# mcu.net
KiCad netlist of a schematic drawn in Altium Designer
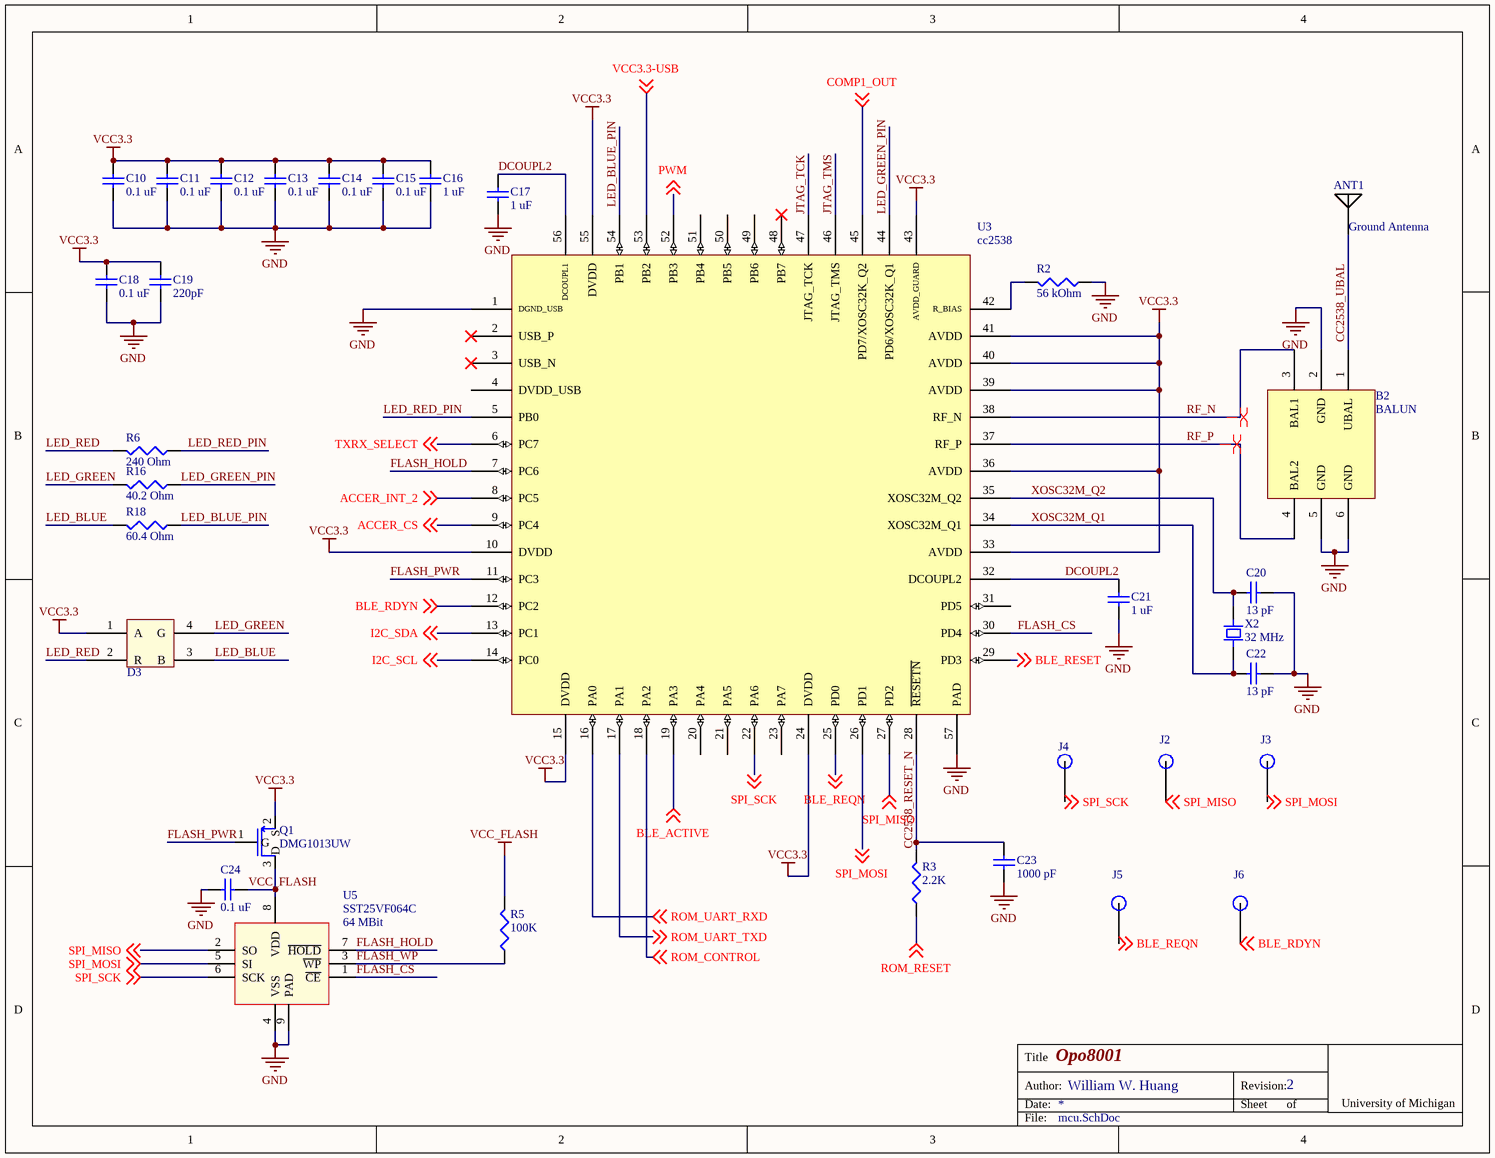
[diagram p0: mcu.SchDoc]

(export (version "E")
  (design (tool "Eeschema 10.0.6"))
  (components
    (comp (ref "ANT1")
      (value "Ground Antenna")
      (footprint "SMD Ground Antenna")
      (description "Molex 2.4 GHz SMD On-Ground Antenna")
      (libsource (lib "opo_general") (part "Molex Antenna"))
    )
    (comp (ref "B2")
      (value "BALUN")
      (footprint "2450BM15A0002")
      (description "Johanson CC253X Balun")
      (fields (field (name "MFR") "Johanson Technology") (field (name "MFR PART NUMBER") "2450BM15A0002"))
      (libsource (lib "opo_general") (part "cc2538_Balun"))
    )
    (comp (ref "C10")
      (value "0.1 uF")
      (footprint "0402")
      (description "Ceramic capacitor, 0.1u, 0402 package")
      (fields (field (name "TOLERANCE") "10%") (field (name "Comment") "Ceramic capacitor"))
      (libsource (lib "rlc") (part "C_0.1u_0402_ceramic"))
    )
    (comp (ref "C11")
      (value "0.1 uF")
      (footprint "0402")
      (description "Ceramic capacitor, 0.1u, 0402 package")
      (fields (field (name "TOLERANCE") "10%") (field (name "Comment") "Ceramic capacitor"))
      (libsource (lib "rlc") (part "C_0.1u_0402_ceramic"))
    )
    (comp (ref "C12")
      (value "0.1 uF")
      (footprint "0402")
      (description "Ceramic capacitor, 0.1u, 0402 package")
      (fields (field (name "TOLERANCE") "10%") (field (name "Comment") "Ceramic capacitor"))
      (libsource (lib "rlc") (part "C_0.1u_0402_ceramic"))
    )
    (comp (ref "C13")
      (value "0.1 uF")
      (footprint "0402")
      (description "Ceramic capacitor, 0.1u, 0402 package")
      (fields (field (name "TOLERANCE") "10%") (field (name "Comment") "Ceramic capacitor"))
      (libsource (lib "rlc") (part "C_0.1u_0402_ceramic"))
    )
    (comp (ref "C14")
      (value "0.1 uF")
      (footprint "0402")
      (description "Ceramic capacitor, 0.1u, 0402 package")
      (fields (field (name "TOLERANCE") "10%") (field (name "Comment") "Ceramic capacitor"))
      (libsource (lib "rlc") (part "C_0.1u_0402_ceramic"))
    )
    (comp (ref "C15")
      (value "0.1 uF")
      (footprint "0402")
      (description "Ceramic capacitor, 0.1u, 0402 package")
      (fields (field (name "TOLERANCE") "10%") (field (name "Comment") "Ceramic capacitor"))
      (libsource (lib "rlc") (part "C_0.1u_0402_ceramic"))
    )
    (comp (ref "C16")
      (value "1 uF")
      (footprint "0402")
      (description "Ceramic capacitor, 1 uF, 0402 package")
      (fields (field (name "TOLERANCE") "10%") (field (name "Comment") "Ceramic capacitor"))
      (libsource (lib "rlc") (part "C_1u_0402_ceramic"))
    )
    (comp (ref "C17")
      (value "1 uF")
      (footprint "0402")
      (description "Ceramic capacitor, 1 uF, 0402 package")
      (fields (field (name "TOLERANCE") "10%") (field (name "Comment") "Ceramic capacitor"))
      (libsource (lib "rlc") (part "C_1u_0402_ceramic"))
    )
    (comp (ref "C18")
      (value "0.1 uF")
      (footprint "0402")
      (description "Ceramic capacitor, 0.1u, 0402 package")
      (fields (field (name "TOLERANCE") "10%") (field (name "Comment") "Ceramic capacitor"))
      (libsource (lib "rlc") (part "C_0.1u_0402_ceramic"))
    )
    (comp (ref "C19")
      (value "220pF")
      (footprint "0402")
      (description "220pF 5% 50 V C0G NP0 0402 ceramic cap")
      (fields (field (name "MFR") "Murata") (field (name "MFR PART NUMBER") "GRM1555C1H221JA01D"))
      (libsource (lib "rlc") (part "C_220pf_0402_ceramic"))
    )
    (comp (ref "C20")
      (value "13 pF")
      (footprint "0402")
      (description "13pf, 50V, 2%, c0G, NP0, 0402, ceramic")
      (fields (field (name "MFR") "Murata") (field (name "MFR PART NUMBER") "GRM1555C1H130GA01D"))
      (libsource (lib "rlc") (part "C_13p_0402"))
    )
    (comp (ref "C21")
      (value "1 uF")
      (footprint "0402")
      (description "Ceramic capacitor, 1 uF, 0402 package")
      (fields (field (name "TOLERANCE") "10%") (field (name "Comment") "Ceramic capacitor"))
      (libsource (lib "rlc") (part "C_1u_0402_ceramic"))
    )
    (comp (ref "C22")
      (value "13 pF")
      (footprint "0402")
      (description "13pf, 50V, 2%, c0G, NP0, 0402, ceramic")
      (fields (field (name "MFR") "Murata") (field (name "MFR PART NUMBER") "GRM1555C1H130GA01D"))
      (libsource (lib "rlc") (part "C_13p_0402"))
    )
    (comp (ref "C23")
      (value "1000 pF")
      (footprint "0402")
      (description "Ceramic capacitor, 1000 pF, 0402 package")
      (fields (field (name "TOLERANCE") "10%") (field (name "Comment") "Ceramic capacitor"))
      (libsource (lib "rlc") (part "C_1000p_0402_ceramic"))
    )
    (comp (ref "C24")
      (value "0.1 uF")
      (footprint "0402")
      (description "Ceramic capacitor, 0.1u, 0402 package")
      (fields (field (name "TOLERANCE") "10%") (field (name "Comment") "Ceramic capacitor"))
      (libsource (lib "rlc") (part "C_0.1u_0402_ceramic"))
    )
    (comp (ref "D3")
      (value "Tri Color LED")
      (footprint "0404")
      (description "LED, RGB, 0404")
      (libsource (lib "rlc") (part "D_LED_RGB_0404"))
    )
    (comp (ref "J2")
      (value "RCU 0603 SMD Testpoint")
      (footprint "RCU_0603")
      (description "0603 SMD Testpoint")
      (libsource (lib "connectors") (part "Testpoint-0603"))
    )
    (comp (ref "J3")
      (value "RCU 0603 SMD Testpoint")
      (footprint "RCU_0603")
      (description "0603 SMD Testpoint")
      (libsource (lib "connectors") (part "Testpoint-0603"))
    )
    (comp (ref "J4")
      (value "RCU 0603 SMD Testpoint")
      (footprint "RCU_0603")
      (description "0603 SMD Testpoint")
      (libsource (lib "connectors") (part "Testpoint-0603"))
    )
    (comp (ref "J5")
      (value "RCU 0603 SMD Testpoint")
      (footprint "RCU_0603")
      (description "0603 SMD Testpoint")
      (libsource (lib "connectors") (part "Testpoint-0603"))
    )
    (comp (ref "J6")
      (value "RCU 0603 SMD Testpoint")
      (footprint "RCU_0603")
      (description "0603 SMD Testpoint")
      (libsource (lib "connectors") (part "Testpoint-0603"))
    )
    (comp (ref "Q1")
      (value "DMG1013UW")
      (footprint "SC70-3")
      (description "P-CHANNEL ENHANCEMENT MODE MOSFET")
      (libsource (lib "opo_general") (part "DMG1013UW"))
    )
    (comp (ref "R2")
      (value "56 kOhm")
      (footprint "0402")
      (description "56 kOhm, 1%, .0603 W, 0402")
      (fields (field (name "MFR") "Rohm") (field (name "MFR PART NUMBER") "MCR01MRTF5602"))
      (libsource (lib "rlc") (part "R_56K_0402"))
    )
    (comp (ref "R3")
      (value "2.2K")
      (footprint "0402")
      (description "Chip resistor, 2.2K, 0402 package")
      (fields (field (name "TOLERANCE") "1%") (field (name "POWER") "1/16 W"))
      (libsource (lib "rlc") (part "R_2.2K_0402"))
    )
    (comp (ref "R5")
      (value "100K")
      (footprint "0402")
      (description "Chip resistor, 100K, 0402 package")
      (fields (field (name "TOLERANCE") "1%") (field (name "POWER") "1/16 W"))
      (libsource (lib "rlc") (part "R_100K_0402"))
    )
    (comp (ref "R6")
      (value "240 Ohm")
      (footprint "0402")
      (description "240 Ohm, 1%, .05W, 0402 Chip Resistor")
      (fields (field (name "Comment") "Chip resistor"))
      (libsource (lib "rlc") (part "R_240_0402"))
    )
    (comp (ref "R16")
      (value "40.2 Ohm")
      (footprint "0402")
      (description "40.2 Ohm 0402 1% Chip Resistor")
      (fields (field (name "Comment") "Chip Resistor"))
      (libsource (lib "rlc") (part "R_40.2_0402"))
    )
    (comp (ref "R18")
      (value "60.4 Ohm")
      (footprint "0402")
      (description "60.4 Ohm, .05W, 1% 0402 Chip Resistor")
      (fields (field (name "Comment") "Chip resistor"))
      (libsource (lib "rlc") (part "R_60.4_0402"))
    )
    (comp (ref "U3")
      (value "cc2538")
      (footprint "QFN50P800X800X100_HS-57N")
      (description "cc2538 MCU/802.15.4 radio")
      (libsource (lib "opo_general") (part "cc2538"))
    )
    (comp (ref "U5")
      (value "SST25VF064C")
      (footprint "WSON")
      (description "64 Mbit SPI Serial Dual I/O Flash")
      (fields (field (name "CAPACITY") "64 MBit"))
      (libsource (lib "opo_general") (part "SST25VF064C"))
    )
    (comp (ref "X2")
      (value "32 MHz")
      (footprint "FA-128")
      (description "32MHz, 10ppm, 10pF, 60 Ohm")
      (fields (field (name "MFR") "Epson") (field (name "MFR PART NUMBER") "FA-128 32.0000MF20X-K3"))
      (libsource (lib "opo_general") (part "X_32M_FA-128"))
    )
  )
  (nets
    (net (code "1") (name "/CC2538_RESET_N") (class "Default")
      (node (ref "C23") (pin "1") (pintype "passive"))
      (node (ref "R3") (pin "1") (pintype "passive"))
      (node (ref "U3") (pin "28") (pinfunction "~{RESETN}_28") (pintype "passive"))
    )
    (net (code "2") (name "/CC2538_UBAL") (class "Default")
      (node (ref "ANT1") (pin "1") (pintype "passive"))
      (node (ref "B2") (pin "1") (pinfunction "UBAL_1") (pintype "passive"))
    )
    (net (code "3") (name "/DCOUPL2") (class "Default")
      (node (ref "C17") (pin "1") (pintype "passive"))
      (node (ref "C21") (pin "1") (pintype "passive"))
      (node (ref "U3") (pin "32") (pinfunction "DCOUPL2_32") (pintype "power_in"))
      (node (ref "U3") (pin "56") (pinfunction "DCOUPL1_56") (pintype "power_in"))
    )
    (net (code "4") (name "/FLASH_CS") (class "Default")
      (node (ref "U3") (pin "30") (pinfunction "PD4_30") (pintype "bidirectional"))
      (node (ref "U5") (pin "1") (pinfunction "~{CE}_1") (pintype "passive"))
    )
    (net (code "5") (name "/FLASH_HOLD") (class "Default")
      (node (ref "U3") (pin "7") (pinfunction "PC6_7") (pintype "bidirectional"))
      (node (ref "U5") (pin "7") (pinfunction "~{HOLD}_7") (pintype "passive"))
    )
    (net (code "6") (name "/FLASH_PWR") (class "Default")
      (node (ref "Q1") (pin "1") (pinfunction "G_1") (pintype "passive"))
      (node (ref "U3") (pin "11") (pinfunction "PC3_11") (pintype "bidirectional"))
    )
    (net (code "7") (name "/FLASH_WP") (class "Default")
      (node (ref "R5") (pin "2") (pintype "passive"))
      (node (ref "U5") (pin "3") (pinfunction "~{WP}_3") (pintype "passive"))
    )
    (net (code "8") (name "/JTAG_TCK") (class "Default")
      (node (ref "U3") (pin "47") (pinfunction "JTAG_TCK_47") (pintype "passive"))
    )
    (net (code "9") (name "/JTAG_TMS") (class "Default")
      (node (ref "U3") (pin "46") (pinfunction "JTAG_TMS_46") (pintype "passive"))
    )
    (net (code "10") (name "/LED_BLUE") (class "Default")
      (node (ref "D3") (pin "3") (pinfunction "B_3") (pintype "passive"))
      (node (ref "R18") (pin "1") (pintype "passive"))
    )
    (net (code "11") (name "/LED_BLUE_PIN") (class "Default")
      (node (ref "R18") (pin "2") (pintype "passive"))
      (node (ref "U3") (pin "54") (pinfunction "PB1_54") (pintype "bidirectional"))
    )
    (net (code "12") (name "/LED_GREEN") (class "Default")
      (node (ref "D3") (pin "4") (pinfunction "G_4") (pintype "passive"))
      (node (ref "R16") (pin "1") (pintype "passive"))
    )
    (net (code "13") (name "/LED_GREEN_PIN") (class "Default")
      (node (ref "R16") (pin "2") (pintype "passive"))
      (node (ref "U3") (pin "44") (pinfunction "PD6/XOSC32K_Q1_44") (pintype "passive"))
    )
    (net (code "14") (name "/LED_RED") (class "Default")
      (node (ref "D3") (pin "2") (pinfunction "R_2") (pintype "passive"))
      (node (ref "R6") (pin "1") (pintype "passive"))
    )
    (net (code "15") (name "/LED_RED_PIN") (class "Default")
      (node (ref "R6") (pin "2") (pintype "passive"))
      (node (ref "U3") (pin "5") (pinfunction "PB0_5") (pintype "passive"))
    )
    (net (code "16") (name "/RF_N") (class "Default")
      (node (ref "B2") (pin "3") (pinfunction "BAL1_3") (pintype "passive"))
      (node (ref "U3") (pin "38") (pinfunction "RF_N_38") (pintype "passive"))
    )
    (net (code "17") (name "/RF_P") (class "Default")
      (node (ref "B2") (pin "4") (pinfunction "BAL2_4") (pintype "passive"))
      (node (ref "U3") (pin "37") (pinfunction "RF_P_37") (pintype "passive"))
    )
    (net (code "18") (name "/XOSC32M_Q1") (class "Default")
      (node (ref "C22") (pin "2") (pintype "passive"))
      (node (ref "U3") (pin "34") (pinfunction "XOSC32M_Q1_34") (pintype "passive"))
      (node (ref "X2") (pin "3") (pintype "passive"))
    )
    (net (code "19") (name "/XOSC32M_Q2") (class "Default")
      (node (ref "C20") (pin "1") (pintype "passive"))
      (node (ref "U3") (pin "35") (pinfunction "XOSC32M_Q2_35") (pintype "passive"))
      (node (ref "X2") (pin "1") (pintype "passive"))
    )
    (net (code "20") (name "ACCER_CS") (class "Default")
      (node (ref "U3") (pin "9") (pinfunction "PC4_9") (pintype "bidirectional"))
    )
    (net (code "21") (name "ACCER_INT_2") (class "Default")
      (node (ref "U3") (pin "8") (pinfunction "PC5_8") (pintype "bidirectional"))
    )
    (net (code "22") (name "BLE_ACTIVE") (class "Default")
      (node (ref "U3") (pin "19") (pinfunction "PA3_19") (pintype "bidirectional"))
    )
    (net (code "23") (name "BLE_RDYN") (class "Default")
      (node (ref "J6") (pin "1") (pinfunction "J_1") (pintype "passive"))
      (node (ref "U3") (pin "12") (pinfunction "PC2_12") (pintype "bidirectional"))
    )
    (net (code "24") (name "BLE_REQN") (class "Default")
      (node (ref "J5") (pin "1") (pinfunction "J_1") (pintype "passive"))
      (node (ref "U3") (pin "25") (pinfunction "PD0_25") (pintype "bidirectional"))
    )
    (net (code "25") (name "BLE_RESET") (class "Default")
      (node (ref "U3") (pin "29") (pinfunction "PD3_29") (pintype "bidirectional"))
    )
    (net (code "26") (name "COMP1_OUT") (class "Default")
      (node (ref "U3") (pin "45") (pinfunction "PD7/XOSC32K_Q2_45") (pintype "passive"))
    )
    (net (code "27") (name "GND") (class "Default")
      (node (ref "B2") (pin "2") (pinfunction "GND_2") (pintype "passive"))
      (node (ref "B2") (pin "5") (pinfunction "GND_5") (pintype "passive"))
      (node (ref "B2") (pin "6") (pinfunction "GND_6") (pintype "passive"))
      (node (ref "C10") (pin "2") (pintype "passive"))
      (node (ref "C11") (pin "2") (pintype "passive"))
      (node (ref "C12") (pin "2") (pintype "passive"))
      (node (ref "C13") (pin "2") (pintype "passive"))
      (node (ref "C14") (pin "2") (pintype "passive"))
      (node (ref "C15") (pin "2") (pintype "passive"))
      (node (ref "C16") (pin "2") (pintype "passive"))
      (node (ref "C17") (pin "2") (pintype "passive"))
      (node (ref "C18") (pin "2") (pintype "passive"))
      (node (ref "C19") (pin "2") (pintype "passive"))
      (node (ref "C20") (pin "2") (pintype "passive"))
      (node (ref "C21") (pin "2") (pintype "passive"))
      (node (ref "C22") (pin "1") (pintype "passive"))
      (node (ref "C23") (pin "2") (pintype "passive"))
      (node (ref "C24") (pin "1") (pintype "passive"))
      (node (ref "R2") (pin "2") (pintype "passive"))
      (node (ref "U3") (pin "1") (pinfunction "DGND_USB_1") (pintype "passive"))
      (node (ref "U3") (pin "57") (pinfunction "PAD_57") (pintype "passive"))
      (node (ref "U5") (pin "4") (pinfunction "VSS_4") (pintype "passive"))
      (node (ref "U5") (pin "9") (pinfunction "PAD_9") (pintype "passive"))
    )
    (net (code "28") (name "I2C_SCL") (class "Default")
      (node (ref "U3") (pin "14") (pinfunction "PC0_14") (pintype "bidirectional"))
    )
    (net (code "29") (name "I2C_SDA") (class "Default")
      (node (ref "U3") (pin "13") (pinfunction "PC1_13") (pintype "bidirectional"))
    )
    (net (code "30") (name "Net-(U3-R_BIAS)") (class "Default")
      (node (ref "R2") (pin "1") (pintype "passive"))
      (node (ref "U3") (pin "42") (pinfunction "R_BIAS_42") (pintype "passive"))
    )
    (net (code "31") (name "PWM") (class "Default")
      (node (ref "U3") (pin "52") (pinfunction "PB3_52") (pintype "bidirectional"))
    )
    (net (code "32") (name "ROM_CONTROL") (class "Default")
      (node (ref "U3") (pin "18") (pinfunction "PA2_18") (pintype "bidirectional"))
    )
    (net (code "33") (name "ROM_RESET") (class "Default") (node (ref "R3") (pin "2") (pintype "passive")))
    (net (code "34") (name "ROM_UART_RXD") (class "Default")
      (node (ref "U3") (pin "16") (pinfunction "PA0_16") (pintype "bidirectional"))
    )
    (net (code "35") (name "ROM_UART_TXD") (class "Default")
      (node (ref "U3") (pin "17") (pinfunction "PA1_17") (pintype "bidirectional"))
    )
    (net (code "36") (name "SPI_MISO") (class "Default")
      (node (ref "J2") (pin "1") (pinfunction "J_1") (pintype "passive"))
      (node (ref "U3") (pin "27") (pinfunction "PD2_27") (pintype "bidirectional"))
      (node (ref "U5") (pin "2") (pinfunction "SO_2") (pintype "passive"))
    )
    (net (code "37") (name "SPI_MOSI") (class "Default")
      (node (ref "J3") (pin "1") (pinfunction "J_1") (pintype "passive"))
      (node (ref "U3") (pin "26") (pinfunction "PD1_26") (pintype "bidirectional"))
      (node (ref "U5") (pin "5") (pinfunction "SI_5") (pintype "passive"))
    )
    (net (code "38") (name "SPI_SCK") (class "Default")
      (node (ref "J4") (pin "1") (pinfunction "J_1") (pintype "passive"))
      (node (ref "U3") (pin "22") (pinfunction "PA6_22") (pintype "bidirectional"))
      (node (ref "U5") (pin "6") (pinfunction "SCK_6") (pintype "passive"))
    )
    (net (code "39") (name "TXRX_SELECT") (class "Default")
      (node (ref "U3") (pin "6") (pinfunction "PC7_6") (pintype "bidirectional"))
    )
    (net (code "40") (name "VCC3.3") (class "Default")
      (node (ref "C10") (pin "1") (pintype "passive"))
      (node (ref "C11") (pin "1") (pintype "passive"))
      (node (ref "C12") (pin "1") (pintype "passive"))
      (node (ref "C13") (pin "1") (pintype "passive"))
      (node (ref "C14") (pin "1") (pintype "passive"))
      (node (ref "C15") (pin "1") (pintype "passive"))
      (node (ref "C16") (pin "1") (pintype "passive"))
      (node (ref "C18") (pin "1") (pintype "passive"))
      (node (ref "C19") (pin "1") (pintype "passive"))
      (node (ref "D3") (pin "1") (pinfunction "A_1") (pintype "passive"))
      (node (ref "Q1") (pin "2") (pinfunction "S_2") (pintype "passive"))
      (node (ref "U3") (pin "10") (pinfunction "DVDD_10") (pintype "power_in"))
      (node (ref "U3") (pin "15") (pinfunction "DVDD_15") (pintype "power_in"))
      (node (ref "U3") (pin "24") (pinfunction "DVDD_24") (pintype "power_in"))
      (node (ref "U3") (pin "33") (pinfunction "AVDD_33") (pintype "power_in"))
      (node (ref "U3") (pin "36") (pinfunction "AVDD_36") (pintype "power_in"))
      (node (ref "U3") (pin "39") (pinfunction "AVDD_39") (pintype "power_in"))
      (node (ref "U3") (pin "40") (pinfunction "AVDD_40") (pintype "power_in"))
      (node (ref "U3") (pin "41") (pinfunction "AVDD_41") (pintype "power_in"))
      (node (ref "U3") (pin "43") (pinfunction "AVDD_GUARD_43") (pintype "power_in"))
      (node (ref "U3") (pin "55") (pinfunction "DVDD_55") (pintype "power_in"))
    )
    (net (code "41") (name "VCC3.3-USB") (class "Default")
      (node (ref "U3") (pin "53") (pinfunction "PB2_53") (pintype "bidirectional"))
    )
    (net (code "42") (name "VCC_FLASH") (class "Default")
      (node (ref "C24") (pin "2") (pintype "passive"))
      (node (ref "Q1") (pin "3") (pinfunction "D_3") (pintype "passive"))
      (node (ref "R5") (pin "1") (pintype "passive"))
      (node (ref "U5") (pin "8") (pinfunction "VDD_8") (pintype "passive"))
    )
    (net (code "43") (name "unconnected-(U3-DVDD_USB-Pad4)") (class "Default")
      (node (ref "U3") (pin "4") (pinfunction "DVDD_USB_4") (pintype "passive"))
    )
    (net (code "44") (name "unconnected-(U3-PA4-Pad20)") (class "Default")
      (node (ref "U3") (pin "20") (pinfunction "PA4_20") (pintype "bidirectional"))
    )
    (net (code "45") (name "unconnected-(U3-PA5-Pad21)") (class "Default")
      (node (ref "U3") (pin "21") (pinfunction "PA5_21") (pintype "bidirectional"))
    )
    (net (code "46") (name "unconnected-(U3-PA7-Pad23)") (class "Default")
      (node (ref "U3") (pin "23") (pinfunction "PA7_23") (pintype "bidirectional"))
    )
    (net (code "47") (name "unconnected-(U3-PB4-Pad51)") (class "Default")
      (node (ref "U3") (pin "51") (pinfunction "PB4_51") (pintype "bidirectional"))
    )
    (net (code "48") (name "unconnected-(U3-PB5-Pad50)") (class "Default")
      (node (ref "U3") (pin "50") (pinfunction "PB5_50") (pintype "bidirectional"))
    )
    (net (code "49") (name "unconnected-(U3-PB6-Pad49)") (class "Default")
      (node (ref "U3") (pin "49") (pinfunction "PB6_49") (pintype "bidirectional"))
    )
    (net (code "50") (name "unconnected-(U3-PB7-Pad48)") (class "Default")
      (node (ref "U3") (pin "48") (pinfunction "PB7_48") (pintype "bidirectional+no_connect"))
    )
    (net (code "51") (name "unconnected-(U3-PD5-Pad31)") (class "Default")
      (node (ref "U3") (pin "31") (pinfunction "PD5_31") (pintype "bidirectional"))
    )
    (net (code "52") (name "unconnected-(U3-USB_N-Pad3)") (class "Default")
      (node (ref "U3") (pin "3") (pinfunction "USB_N_3") (pintype "passive+no_connect"))
    )
    (net (code "53") (name "unconnected-(U3-USB_P-Pad2)") (class "Default")
      (node (ref "U3") (pin "2") (pinfunction "USB_P_2") (pintype "passive+no_connect"))
    )
  )
)
